# 6_Bluetooth.net
KiCad netlist of a schematic drawn in Altium Designer
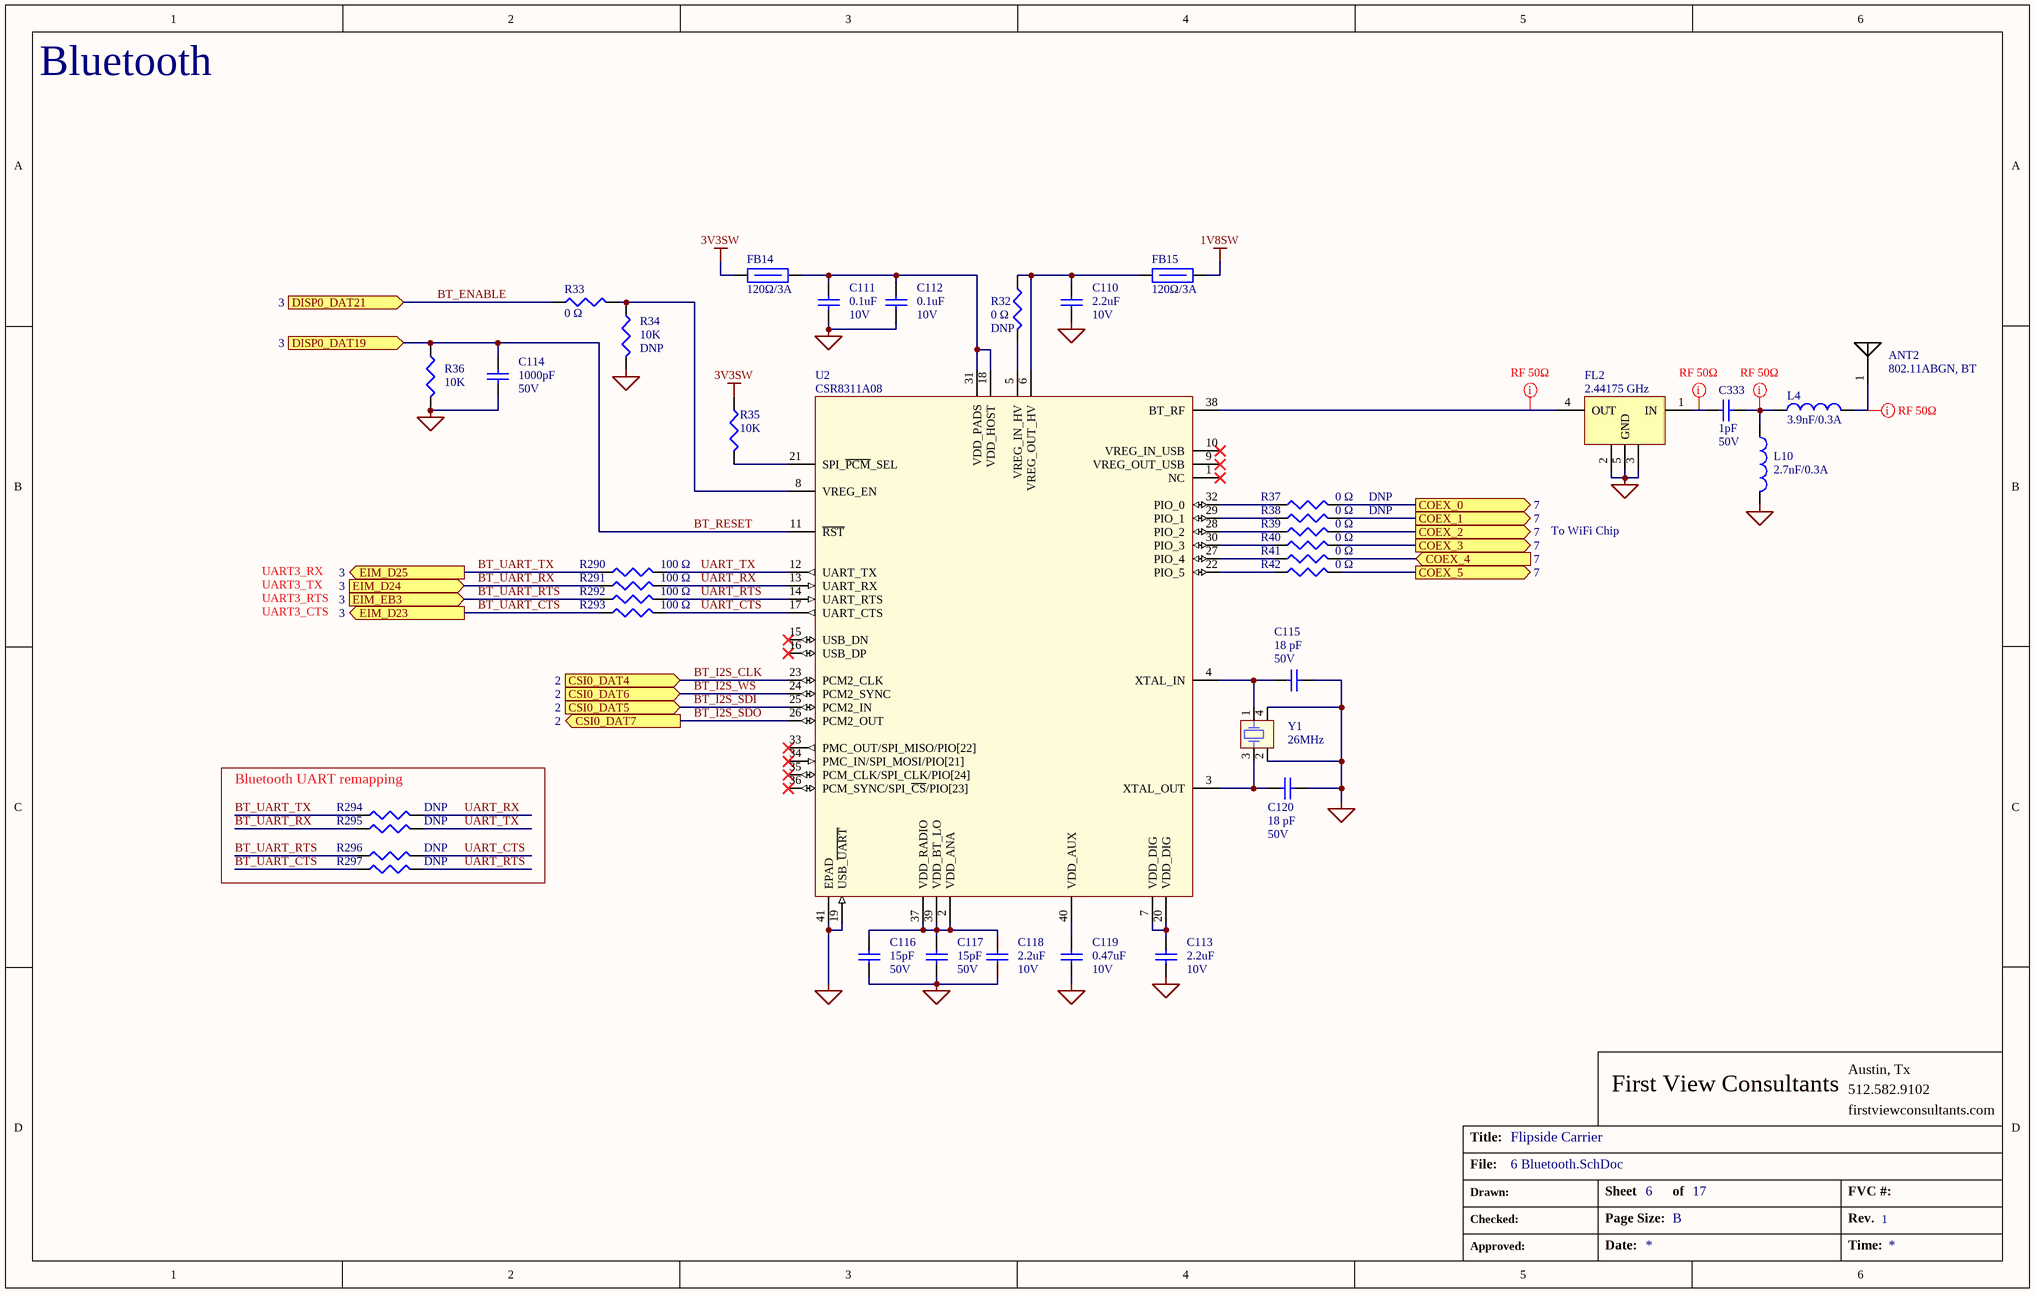
[diagram p0: 6 Bluetooth.SchDoc]

(export (version "E")
  (design (tool "Eeschema 10.0.6"))
  (components
    (comp (ref "ANT2")
      (value "802.11ABGN, BT")
      (footprint "ANT_2450AT18A100E")
      (description "Antenna, WiFi/BT, SMD")
      (fields
        (field (name "MANUFACTURER") "Johanson Technology, Inc.")
        (field (name "Comment") "2450AT18A100E")
      )
      (libsource (lib "Firstview") (part "2450AT18A100E"))
    )
    (comp (ref "C110")
      (value "2.2uF")
      (footprint "CAP_0402")
      (description "Cap, Cer, 2.2uF, 10V, 10%, X5R, 0402")
      (fields
        (field (name "VOLTAGE") "10V")
        (field (name "MANUFACTURER") "Kemet")
        (field (name "Comment") "Cap 2.2uF 10V 0402")
      )
      (libsource (lib "Firstview") (part "Cap 2.2uF 10V 0402"))
    )
    (comp (ref "C111")
      (value "0.1uF")
      (footprint "CAP_0402")
      (description "Cap, Cer, 0.1uF, 10V, 10%, X5R, 0402")
      (fields
        (field (name "TOLERANCE") "±10%")
        (field (name "MANUFACTURER") "Murata Electronics North America")
        (field (name "VOLTAGE") "10V")
      )
      (libsource (lib "Firstview") (part "Cap 0.1uF 10V 0402"))
    )
    (comp (ref "C112")
      (value "0.1uF")
      (footprint "CAP_0402")
      (description "Cap, Cer, 0.1uF, 10V, 10%, X5R, 0402")
      (fields
        (field (name "TOLERANCE") "±10%")
        (field (name "MANUFACTURER") "Murata Electronics North America")
        (field (name "VOLTAGE") "10V")
      )
      (libsource (lib "Firstview") (part "Cap 0.1uF 10V 0402"))
    )
    (comp (ref "C113")
      (value "2.2uF")
      (footprint "CAP_0402")
      (description "Cap, Cer, 2.2uF, 10V, 10%, X5R, 0402")
      (fields
        (field (name "VOLTAGE") "10V")
        (field (name "MANUFACTURER") "Kemet")
        (field (name "Comment") "Cap 2.2uF 10V 0402")
      )
      (libsource (lib "Firstview") (part "Cap 2.2uF 10V 0402"))
    )
    (comp (ref "C114")
      (value "1000pF")
      (footprint "CAP_0603")
      (description "Cap, Cer, 1000pF, 50V, 10%, X7S, 0603")
      (fields
        (field (name "TOLERANCE") "10%")
        (field (name "MANUFACTURER") "Yageo")
        (field (name "VOLTAGE") "50V")
      )
      (libsource (lib "Firstview") (part "Cap 1000pF 50V 0603"))
    )
    (comp (ref "C115")
      (value "18 pF")
      (footprint "CAP_0402")
      (description "Cap, Cer, 18pF, 50V, 5%, C0G, 0402")
      (fields
        (field (name "MANUFACTURER") "TDK Corporation")
        (field (name "VOLTAGE") "50V")
        (field (name "Comment") "Cap 18pF 50V 0402")
      )
      (libsource (lib "Firstview") (part "Cap 18pF 50V 0402"))
    )
    (comp (ref "C116")
      (value "15pF")
      (footprint "CAP_0402")
      (description "Cap, Cer, 15pF, 50V, 5%, C0G/NP0, 0402")
      (fields
        (field (name "TOLERANCE") "5%")
        (field (name "MANUFACTURER") "Murata Electronics North America")
        (field (name "VOLTAGE") "50V")
      )
      (libsource (lib "Firstview") (part "Cap 15pF 50V 0402"))
    )
    (comp (ref "C117")
      (value "15pF")
      (footprint "CAP_0402")
      (description "Cap, Cer, 15pF, 50V, 5%, C0G/NP0, 0402")
      (fields
        (field (name "TOLERANCE") "5%")
        (field (name "MANUFACTURER") "Murata Electronics North America")
        (field (name "VOLTAGE") "50V")
      )
      (libsource (lib "Firstview") (part "Cap 15pF 50V 0402"))
    )
    (comp (ref "C118")
      (value "2.2uF")
      (footprint "CAP_0402")
      (description "Cap, Cer, 2.2uF, 10V, 10%, X5R, 0402")
      (fields
        (field (name "VOLTAGE") "10V")
        (field (name "MANUFACTURER") "Kemet")
        (field (name "Comment") "Cap 2.2uF 10V 0402")
      )
      (libsource (lib "Firstview") (part "Cap 2.2uF 10V 0402"))
    )
    (comp (ref "C119")
      (value "0.47uF")
      (footprint "CAP_0402")
      (description "Cap, Cer, 0.47uF, 10V, 10%, X5R, 0402")
      (fields
        (field (name "MANUFACTURER") "TDK Corporation")
        (field (name "TOLERANCE") "±10%")
        (field (name "VOLTAGE") "10V")
      )
      (libsource (lib "Firstview") (part "Cap 0.47uF 10V 0402"))
    )
    (comp (ref "C120")
      (value "18 pF")
      (footprint "CAP_0402")
      (description "Cap, Cer, 18pF, 50V, 5%, C0G, 0402")
      (fields
        (field (name "MANUFACTURER") "TDK Corporation")
        (field (name "VOLTAGE") "50V")
        (field (name "Comment") "Cap 18pF 50V 0402")
      )
      (libsource (lib "Firstview") (part "Cap 18pF 50V 0402"))
    )
    (comp (ref "C333")
      (value "1pF")
      (footprint "CAP_0402")
      (description "Cap, Cer, 0.1uF, 50V, 10%, X5R, 0402")
      (fields
        (field (name "TOLERANCE") "±10%")
        (field (name "MANUFACTURER") "Kemet")
        (field (name "VOLTAGE") "50V")
      )
      (libsource (lib "Firstview") (part "Cap 1pF 50V 0402 RF"))
    )
    (comp (ref "FB14")
      (value "120Ω/3A")
      (footprint "IND_0603")
      (description "Ind, Ferrite Bead, 120R, 20mOhm, 3A, 0603")
      (fields
        (field (name "MANUFACTURER") "Murata Electronics North America")
        (field (name "Comment") "BLM18KG121TN1D")
      )
      (libsource (lib "Firstview") (part "BLM18KG121TN1D"))
    )
    (comp (ref "FB15")
      (value "120Ω/3A")
      (footprint "IND_0603")
      (description "Ind, Ferrite Bead, 120R, 20mOhm, 3A, 0603")
      (fields
        (field (name "MANUFACTURER") "Murata Electronics North America")
        (field (name "Comment") "BLM18KG121TN1D")
      )
      (libsource (lib "Firstview") (part "BLM18KG121TN1D"))
    )
    (comp (ref "FL2")
      (value "2.44175 GHz")
      (footprint "SMD(1.3x1.1)_B39242B9413K610")
      (description "Filter, Saw, 2.44175 GHz, BT, SMD")
      (fields (field (name "MANUFACTURER") "EPCOS (TDK)") (field (name "Comment") "B39242B9413K610"))
      (libsource (lib "Firstview") (part "B39242B9413K610"))
    )
    (comp (ref "L4")
      (value "3.9nF/0.3A")
      (footprint "IND_RF_0402")
      (description "Ind, RF, 3.9nH, 0.3A, 220 mOhm, 0402")
      (fields (field (name "MANUFACTURER") "Johanson Technology Inc") (field (name "Comment") "L-07C3N9SV6T"))
      (libsource (lib "Firstview") (part "L-07C3N9SV6T"))
    )
    (comp (ref "L10")
      (value "2.7nF/0.3A")
      (footprint "IND_RF_0402")
      (description "Ind, RF, 2.7nH, 0.3A, 170 mOhm, 0402")
      (fields (field (name "MANUFACTURER") "Johanson Technology Inc") (field (name "Comment") "L-07C2N7SV6T"))
      (libsource (lib "Firstview") (part "L-07C2N7SV6T"))
    )
    (comp (ref "R32")
      (value "0 Ω")
      (footprint "RES_0402")
      (description "Res, 0 ohm, 1/16W, 0402")
      (fields
        (field (name "DNP") "DNP")
        (field (name "MANUFACTURER") "Vishay Dale")
        (field (name "Comment") "Res 0 ohm 0.1W")
      )
      (libsource (lib "Firstview") (part "Res 0 ohm 0.1W"))
    )
    (comp (ref "R33")
      (value "0 Ω")
      (footprint "RES_0402")
      (description "Res, 0 ohm, 1/16W, 0402")
      (fields (field (name "MANUFACTURER") "Vishay Dale") (field (name "Comment") "Res 0 ohm 0.1W"))
      (libsource (lib "Firstview") (part "Res 0 ohm 0.1W"))
    )
    (comp (ref "R34")
      (value "10K")
      (footprint "RES_0402")
      (description "Res, 10K, 1/16W, 1%, 0402")
      (fields
        (field (name "DNP") "DNP")
        (field (name "MANUFACTURER") "Yageo")
        (field (name "Comment") "Res 10K 0.063W")
      )
      (libsource (lib "Firstview") (part "Res 10K 0.063W"))
    )
    (comp (ref "R35")
      (value "10K")
      (footprint "RES_0402")
      (description "Res, 10K, 1/16W, 1%, 0402")
      (fields (field (name "MANUFACTURER") "Yageo") (field (name "Comment") "Res 10K 0.063W"))
      (libsource (lib "Firstview") (part "Res 10K 0.063W"))
    )
    (comp (ref "R36")
      (value "10K")
      (footprint "RES_0402")
      (description "Res, 10K, 1/16W, 1%, 0402")
      (fields (field (name "MANUFACTURER") "Yageo") (field (name "Comment") "Res 10K 0.063W"))
      (libsource (lib "Firstview") (part "Res 10K 0.063W"))
    )
    (comp (ref "R37")
      (value "0 Ω")
      (footprint "RES_0402")
      (description "Res, 0 ohm, 1/16W, 0402")
      (fields
        (field (name "DNP") "DNP")
        (field (name "MANUFACTURER") "Vishay Dale")
        (field (name "Comment") "Res 0 ohm 0.1W")
      )
      (libsource (lib "Firstview") (part "Res 0 ohm 0.1W"))
    )
    (comp (ref "R38")
      (value "0 Ω")
      (footprint "RES_0402")
      (description "Res, 0 ohm, 1/16W, 0402")
      (fields
        (field (name "DNP") "DNP")
        (field (name "MANUFACTURER") "Vishay Dale")
        (field (name "Comment") "Res 0 ohm 0.1W")
      )
      (libsource (lib "Firstview") (part "Res 0 ohm 0.1W"))
    )
    (comp (ref "R39")
      (value "0 Ω")
      (footprint "RES_0402")
      (description "Res, 0 ohm, 1/16W, 0402")
      (fields (field (name "MANUFACTURER") "Vishay Dale") (field (name "Comment") "Res 0 ohm 0.1W"))
      (libsource (lib "Firstview") (part "Res 0 ohm 0.1W"))
    )
    (comp (ref "R40")
      (value "0 Ω")
      (footprint "RES_0402")
      (description "Res, 0 ohm, 1/16W, 0402")
      (fields (field (name "MANUFACTURER") "Vishay Dale") (field (name "Comment") "Res 0 ohm 0.1W"))
      (libsource (lib "Firstview") (part "Res 0 ohm 0.1W"))
    )
    (comp (ref "R41")
      (value "0 Ω")
      (footprint "RES_0402")
      (description "Res, 0 ohm, 1/16W, 0402")
      (fields (field (name "MANUFACTURER") "Vishay Dale") (field (name "Comment") "Res 0 ohm 0.1W"))
      (libsource (lib "Firstview") (part "Res 0 ohm 0.1W"))
    )
    (comp (ref "R42")
      (value "0 Ω")
      (footprint "RES_0402")
      (description "Res, 0 ohm, 1/16W, 0402")
      (fields (field (name "MANUFACTURER") "Vishay Dale") (field (name "Comment") "Res 0 ohm 0.1W"))
      (libsource (lib "Firstview") (part "Res 0 ohm 0.1W"))
    )
    (comp (ref "R290")
      (value "100 Ω")
      (footprint "RES_0402")
      (description "Res, 100R, 0.063W, 1%, 0402")
      (fields
        (field (name "MANUFACTURER") "Murata Electronics North America")
        (field (name "Comment") "Res 100R 0.063W")
      )
      (libsource (lib "Firstview") (part "Res 100R 0.063W"))
    )
    (comp (ref "R291")
      (value "100 Ω")
      (footprint "RES_0402")
      (description "Res, 100R, 0.063W, 1%, 0402")
      (fields
        (field (name "MANUFACTURER") "Murata Electronics North America")
        (field (name "Comment") "Res 100R 0.063W")
      )
      (libsource (lib "Firstview") (part "Res 100R 0.063W"))
    )
    (comp (ref "R292")
      (value "100 Ω")
      (footprint "RES_0402")
      (description "Res, 100R, 0.063W, 1%, 0402")
      (fields
        (field (name "MANUFACTURER") "Murata Electronics North America")
        (field (name "Comment") "Res 100R 0.063W")
      )
      (libsource (lib "Firstview") (part "Res 100R 0.063W"))
    )
    (comp (ref "R293")
      (value "100 Ω")
      (footprint "RES_0402")
      (description "Res, 100R, 0.063W, 1%, 0402")
      (fields
        (field (name "MANUFACTURER") "Murata Electronics North America")
        (field (name "Comment") "Res 100R 0.063W")
      )
      (libsource (lib "Firstview") (part "Res 100R 0.063W"))
    )
    (comp (ref "R294")
      (value "Res 0 ohm 0.1W DNP")
      (footprint "RES_0402")
      (description "Res, 0 ohm, 1/16W, 0402")
      (fields (field (name "MANUFACTURER") "Vishay Dale") (field (name "DNP") "DNP"))
      (libsource (lib "Firstview") (part "Res 0 ohm 0.1W DNP"))
    )
    (comp (ref "R295")
      (value "Res 0 ohm 0.1W DNP")
      (footprint "RES_0402")
      (description "Res, 0 ohm, 1/16W, 0402")
      (fields (field (name "MANUFACTURER") "Vishay Dale") (field (name "DNP") "DNP"))
      (libsource (lib "Firstview") (part "Res 0 ohm 0.1W DNP"))
    )
    (comp (ref "R296")
      (value "Res 0 ohm 0.1W DNP")
      (footprint "RES_0402")
      (description "Res, 0 ohm, 1/16W, 0402")
      (fields (field (name "MANUFACTURER") "Vishay Dale") (field (name "DNP") "DNP"))
      (libsource (lib "Firstview") (part "Res 0 ohm 0.1W DNP"))
    )
    (comp (ref "R297")
      (value "Res 0 ohm 0.1W DNP")
      (footprint "RES_0402")
      (description "Res, 0 ohm, 1/16W, 0402")
      (fields (field (name "MANUFACTURER") "Vishay Dale") (field (name "DNP") "DNP"))
      (libsource (lib "Firstview") (part "Res 0 ohm 0.1W DNP"))
    )
    (comp (ref "U2")
      (value "CSR8311A08")
      (footprint "QFN-40_CSR8311A08")
      (description "IC, Bluetooth, 40-QFN")
      (fields (field (name "MANUFACTURER") "CSR PLC"))
      (libsource (lib "Firstview") (part "CSR8311A08"))
    )
    (comp (ref "Y1")
      (value "26MHz")
      (footprint "DFN(3.2x2.5)_403I35D26M00000")
      (description "Clock, Crystal, 26MHz, 50ppm, 18pf, -40+85°C, SMD")
      (fields
        (field (name "MANUFACTURER") "CTS-Frequency Controls")
        (field (name "Comment") "403I35D26M00000")
      )
      (libsource (lib "Firstview") (part "403I35D26M00000"))
    )
  )
  (nets
    (net (code "1") (name "/BT_ENABLE") (class "Default")
      (node (ref "R33") (pin "1") (pinfunction "1_1") (pintype "passive"))
    )
    (net (code "2") (name "/BT_I2S_CLK") (class "Default")
      (node (ref "U2") (pin "23") (pinfunction "PCM2_CLK_23") (pintype "bidirectional"))
    )
    (net (code "3") (name "/BT_I2S_SDI") (class "Default")
      (node (ref "U2") (pin "25") (pinfunction "PCM2_IN_25") (pintype "bidirectional"))
    )
    (net (code "4") (name "/BT_I2S_SDO") (class "Default")
      (node (ref "U2") (pin "26") (pinfunction "PCM2_OUT_26") (pintype "bidirectional"))
    )
    (net (code "5") (name "/BT_I2S_WS") (class "Default")
      (node (ref "U2") (pin "24") (pinfunction "PCM2_SYNC_24") (pintype "bidirectional"))
    )
    (net (code "6") (name "/BT_RESET") (class "Default")
      (node (ref "C114") (pin "1") (pinfunction "1_1") (pintype "passive"))
      (node (ref "R36") (pin "1") (pinfunction "1_1") (pintype "passive"))
      (node (ref "U2") (pin "11") (pinfunction "~{RST}_11") (pintype "passive"))
    )
    (net (code "7") (name "/BT_UART_CTS") (class "Default")
      (node (ref "R293") (pin "1") (pinfunction "1_1") (pintype "passive"))
      (node (ref "R297") (pin "1") (pinfunction "1_1") (pintype "passive"))
    )
    (net (code "8") (name "/BT_UART_RTS") (class "Default")
      (node (ref "R292") (pin "1") (pinfunction "1_1") (pintype "passive"))
      (node (ref "R296") (pin "1") (pinfunction "1_1") (pintype "passive"))
    )
    (net (code "9") (name "/BT_UART_RX") (class "Default")
      (node (ref "R291") (pin "1") (pinfunction "1_1") (pintype "passive"))
      (node (ref "R295") (pin "1") (pinfunction "1_1") (pintype "passive"))
    )
    (net (code "10") (name "/BT_UART_TX") (class "Default")
      (node (ref "R290") (pin "1") (pinfunction "1_1") (pintype "passive"))
      (node (ref "R294") (pin "1") (pinfunction "1_1") (pintype "passive"))
    )
    (net (code "11") (name "/COEX_0") (class "Default")
      (node (ref "R37") (pin "2") (pinfunction "2_2") (pintype "passive"))
    )
    (net (code "12") (name "/COEX_1") (class "Default")
      (node (ref "R38") (pin "2") (pinfunction "2_2") (pintype "passive"))
    )
    (net (code "13") (name "/COEX_2") (class "Default")
      (node (ref "R39") (pin "2") (pinfunction "2_2") (pintype "passive"))
    )
    (net (code "14") (name "/COEX_3") (class "Default")
      (node (ref "R40") (pin "2") (pinfunction "2_2") (pintype "passive"))
    )
    (net (code "15") (name "/COEX_4") (class "Default")
      (node (ref "R41") (pin "2") (pinfunction "2_2") (pintype "passive"))
    )
    (net (code "16") (name "/COEX_5") (class "Default")
      (node (ref "R42") (pin "2") (pinfunction "2_2") (pintype "passive"))
    )
    (net (code "17") (name "/UART_CTS") (class "Default")
      (node (ref "R293") (pin "2") (pinfunction "2_2") (pintype "passive"))
      (node (ref "R296") (pin "2") (pinfunction "2_2") (pintype "passive"))
      (node (ref "U2") (pin "17") (pinfunction "UART_CTS_17") (pintype "output"))
    )
    (net (code "18") (name "/UART_RTS") (class "Default")
      (node (ref "R292") (pin "2") (pinfunction "2_2") (pintype "passive"))
      (node (ref "R297") (pin "2") (pinfunction "2_2") (pintype "passive"))
      (node (ref "U2") (pin "14") (pinfunction "UART_RTS_14") (pintype "input"))
    )
    (net (code "19") (name "/UART_RX") (class "Default")
      (node (ref "R291") (pin "2") (pinfunction "2_2") (pintype "passive"))
      (node (ref "R294") (pin "2") (pinfunction "2_2") (pintype "passive"))
      (node (ref "U2") (pin "13") (pinfunction "UART_RX_13") (pintype "input"))
    )
    (net (code "20") (name "/UART_TX") (class "Default")
      (node (ref "R290") (pin "2") (pinfunction "2_2") (pintype "passive"))
      (node (ref "R295") (pin "2") (pinfunction "2_2") (pintype "passive"))
      (node (ref "U2") (pin "12") (pinfunction "UART_TX_12") (pintype "output"))
    )
    (net (code "21") (name "1V8SW") (class "Default")
      (node (ref "FB15") (pin "2") (pinfunction "2_2") (pintype "passive"))
    )
    (net (code "22") (name "3V3SW") (class "Default")
      (node (ref "FB14") (pin "1") (pinfunction "1_1") (pintype "passive"))
      (node (ref "R35") (pin "1") (pinfunction "1_1") (pintype "passive"))
    )
    (net (code "23") (name "GND") (class "Default")
      (node (ref "C110") (pin "2") (pinfunction "2_2") (pintype "passive"))
      (node (ref "C111") (pin "2") (pinfunction "2_2") (pintype "passive"))
      (node (ref "C112") (pin "2") (pinfunction "2_2") (pintype "passive"))
      (node (ref "C113") (pin "2") (pinfunction "2_2") (pintype "passive"))
      (node (ref "C114") (pin "2") (pinfunction "2_2") (pintype "passive"))
      (node (ref "C115") (pin "1") (pinfunction "1_1") (pintype "passive"))
      (node (ref "C116") (pin "2") (pinfunction "2_2") (pintype "passive"))
      (node (ref "C117") (pin "2") (pinfunction "2_2") (pintype "passive"))
      (node (ref "C118") (pin "2") (pinfunction "2_2") (pintype "passive"))
      (node (ref "C119") (pin "2") (pinfunction "2_2") (pintype "passive"))
      (node (ref "C120") (pin "1") (pinfunction "1_1") (pintype "passive"))
      (node (ref "FL2") (pin "2") (pinfunction "GND_2") (pintype "power_in"))
      (node (ref "FL2") (pin "3") (pinfunction "GND_3") (pintype "power_in"))
      (node (ref "FL2") (pin "5") (pinfunction "GND_5") (pintype "power_in"))
      (node (ref "L10") (pin "2") (pinfunction "2_2") (pintype "passive"))
      (node (ref "R34") (pin "2") (pinfunction "2_2") (pintype "passive"))
      (node (ref "R36") (pin "2") (pinfunction "2_2") (pintype "passive"))
      (node (ref "U2") (pin "19") (pinfunction "USB_~{UART}_19") (pintype "input"))
      (node (ref "U2") (pin "41") (pinfunction "EPAD_41") (pintype "passive"))
      (node (ref "Y1") (pin "2") (pintype "passive"))
      (node (ref "Y1") (pin "4") (pintype "passive"))
    )
    (net (code "24") (name "Net-(ANT2-Pad1)") (class "Default")
      (node (ref "ANT2") (pin "1") (pinfunction "1_1") (pintype "passive"))
      (node (ref "L4") (pin "2") (pinfunction "2_2") (pintype "passive"))
    )
    (net (code "25") (name "Net-(C113-Pad1)") (class "Default")
      (node (ref "C113") (pin "1") (pinfunction "1_1") (pintype "passive"))
      (node (ref "U2") (pin "20") (pinfunction "VDD_DIG_20") (pintype "passive"))
      (node (ref "U2") (pin "7") (pinfunction "VDD_DIG_7") (pintype "passive"))
    )
    (net (code "26") (name "Net-(C333-Pad2)") (class "Default")
      (node (ref "C333") (pin "2") (pinfunction "2_2") (pintype "passive"))
      (node (ref "L10") (pin "1") (pinfunction "1_1") (pintype "passive"))
      (node (ref "L4") (pin "1") (pinfunction "1_1") (pintype "passive"))
    )
    (net (code "27") (name "Net-(FL2-IN)") (class "Default")
      (node (ref "C333") (pin "1") (pinfunction "1_1") (pintype "passive"))
      (node (ref "FL2") (pin "1") (pinfunction "IN_1") (pintype "power_in"))
    )
    (net (code "28") (name "Net-(FL2-OUT)") (class "Default")
      (node (ref "FL2") (pin "4") (pinfunction "OUT_4") (pintype "power_in"))
      (node (ref "U2") (pin "38") (pinfunction "BT_RF_38") (pintype "passive"))
    )
    (net (code "29") (name "Net-(U2-PIO_0)") (class "Default")
      (node (ref "R37") (pin "1") (pinfunction "1_1") (pintype "passive"))
      (node (ref "U2") (pin "32") (pinfunction "PIO_0_32") (pintype "bidirectional"))
    )
    (net (code "30") (name "Net-(U2-PIO_1)") (class "Default")
      (node (ref "R38") (pin "1") (pinfunction "1_1") (pintype "passive"))
      (node (ref "U2") (pin "29") (pinfunction "PIO_1_29") (pintype "bidirectional"))
    )
    (net (code "31") (name "Net-(U2-PIO_2)") (class "Default")
      (node (ref "R39") (pin "1") (pinfunction "1_1") (pintype "passive"))
      (node (ref "U2") (pin "28") (pinfunction "PIO_2_28") (pintype "bidirectional"))
    )
    (net (code "32") (name "Net-(U2-PIO_3)") (class "Default")
      (node (ref "R40") (pin "1") (pinfunction "1_1") (pintype "passive"))
      (node (ref "U2") (pin "30") (pinfunction "PIO_3_30") (pintype "bidirectional"))
    )
    (net (code "33") (name "Net-(U2-PIO_4)") (class "Default")
      (node (ref "R41") (pin "1") (pinfunction "1_1") (pintype "passive"))
      (node (ref "U2") (pin "27") (pinfunction "PIO_4_27") (pintype "bidirectional"))
    )
    (net (code "34") (name "Net-(U2-PIO_5)") (class "Default")
      (node (ref "R42") (pin "1") (pinfunction "1_1") (pintype "passive"))
      (node (ref "U2") (pin "22") (pinfunction "PIO_5_22") (pintype "bidirectional"))
    )
    (net (code "35") (name "Net-(U2-SPI_~{PCM}_SEL)") (class "Default")
      (node (ref "R35") (pin "2") (pinfunction "2_2") (pintype "passive"))
      (node (ref "U2") (pin "21") (pinfunction "SPI_~{PCM}_SEL_21") (pintype "passive"))
    )
    (net (code "36") (name "Net-(U2-VDD_ANA)") (class "Default")
      (node (ref "C116") (pin "1") (pinfunction "1_1") (pintype "passive"))
      (node (ref "C117") (pin "1") (pinfunction "1_1") (pintype "passive"))
      (node (ref "C118") (pin "1") (pinfunction "1_1") (pintype "passive"))
      (node (ref "U2") (pin "2") (pinfunction "VDD_ANA_2") (pintype "passive"))
      (node (ref "U2") (pin "37") (pinfunction "VDD_RADIO_37") (pintype "passive"))
      (node (ref "U2") (pin "39") (pinfunction "VDD_BT_LO_39") (pintype "passive"))
    )
    (net (code "37") (name "Net-(U2-VDD_AUX)") (class "Default")
      (node (ref "C119") (pin "1") (pinfunction "1_1") (pintype "passive"))
      (node (ref "U2") (pin "40") (pinfunction "VDD_AUX_40") (pintype "passive"))
    )
    (net (code "38") (name "Net-(U2-VDD_HOST)") (class "Default")
      (node (ref "C111") (pin "1") (pinfunction "1_1") (pintype "passive"))
      (node (ref "C112") (pin "1") (pinfunction "1_1") (pintype "passive"))
      (node (ref "FB14") (pin "2") (pinfunction "2_2") (pintype "passive"))
      (node (ref "U2") (pin "18") (pinfunction "VDD_HOST_18") (pintype "passive"))
      (node (ref "U2") (pin "31") (pinfunction "VDD_PADS_31") (pintype "passive"))
    )
    (net (code "39") (name "Net-(U2-VREG_EN)") (class "Default")
      (node (ref "R33") (pin "2") (pinfunction "2_2") (pintype "passive"))
      (node (ref "R34") (pin "1") (pinfunction "1_1") (pintype "passive"))
      (node (ref "U2") (pin "8") (pinfunction "VREG_EN_8") (pintype "passive"))
    )
    (net (code "40") (name "Net-(U2-VREG_IN_HV)") (class "Default")
      (node (ref "R32") (pin "2") (pinfunction "2_2") (pintype "passive"))
      (node (ref "U2") (pin "5") (pinfunction "VREG_IN_HV_5") (pintype "passive"))
    )
    (net (code "41") (name "Net-(U2-VREG_OUT_HV)") (class "Default")
      (node (ref "C110") (pin "1") (pinfunction "1_1") (pintype "passive"))
      (node (ref "FB15") (pin "1") (pinfunction "1_1") (pintype "passive"))
      (node (ref "R32") (pin "1") (pinfunction "1_1") (pintype "passive"))
      (node (ref "U2") (pin "6") (pinfunction "VREG_OUT_HV_6") (pintype "passive"))
    )
    (net (code "42") (name "Net-(U2-XTAL_IN)") (class "Default")
      (node (ref "C115") (pin "2") (pinfunction "2_2") (pintype "passive"))
      (node (ref "U2") (pin "4") (pinfunction "XTAL_IN_4") (pintype "passive"))
      (node (ref "Y1") (pin "1") (pinfunction "OSC1_1") (pintype "passive"))
    )
    (net (code "43") (name "Net-(U2-XTAL_OUT)") (class "Default")
      (node (ref "C120") (pin "2") (pinfunction "2_2") (pintype "passive"))
      (node (ref "U2") (pin "3") (pinfunction "XTAL_OUT_3") (pintype "passive"))
      (node (ref "Y1") (pin "3") (pinfunction "OSC2_3") (pintype "passive"))
    )
    (net (code "44") (name "unconnected-(U2-NC-Pad1)") (class "Default")
      (node (ref "U2") (pin "1") (pinfunction "NC_1") (pintype "passive+no_connect"))
    )
    (net (code "45") (name "unconnected-(U2-PCM_CLK{slash}SPI_CLK{slash}PIO[24]-Pad35)") (class "Default")
      (node (ref "U2") (pin "35") (pinfunction "PCM_CLK/SPI_CLK/PIO[24]_35") (pintype "bidirectional+no_connect"))
    )
    (net (code "46") (name "unconnected-(U2-PCM_SYNC{slash}SPI_~{CS}{slash}PIO[23]-Pad36)") (class "Default")
      (node (ref "U2") (pin "36") (pinfunction "PCM_SYNC/SPI_~{CS}/PIO[23]_36") (pintype "bidirectional+no_connect"))
    )
    (net (code "47") (name "unconnected-(U2-PMC_IN{slash}SPI_MOSI{slash}PIO[21]-Pad34)") (class "Default")
      (node (ref "U2") (pin "34") (pinfunction "PMC_IN/SPI_MOSI/PIO[21]_34") (pintype "input+no_connect"))
    )
    (net (code "48") (name "unconnected-(U2-PMC_OUT{slash}SPI_MISO{slash}PIO[22]-Pad33)") (class "Default")
      (node (ref "U2") (pin "33") (pinfunction "PMC_OUT/SPI_MISO/PIO[22]_33") (pintype "output+no_connect"))
    )
    (net (code "49") (name "unconnected-(U2-USB_DN-Pad15)") (class "Default")
      (node (ref "U2") (pin "15") (pinfunction "USB_DN_15") (pintype "bidirectional+no_connect"))
    )
    (net (code "50") (name "unconnected-(U2-USB_DP-Pad16)") (class "Default")
      (node (ref "U2") (pin "16") (pinfunction "USB_DP_16") (pintype "bidirectional+no_connect"))
    )
    (net (code "51") (name "unconnected-(U2-VREG_IN_USB-Pad10)") (class "Default")
      (node (ref "U2") (pin "10") (pinfunction "VREG_IN_USB_10") (pintype "passive+no_connect"))
    )
    (net (code "52") (name "unconnected-(U2-VREG_OUT_USB-Pad9)") (class "Default")
      (node (ref "U2") (pin "9") (pinfunction "VREG_OUT_USB_9") (pintype "passive+no_connect"))
    )
  )
)
